# Level_Detector.net
KiCad netlist of a schematic drawn in Altium Designer
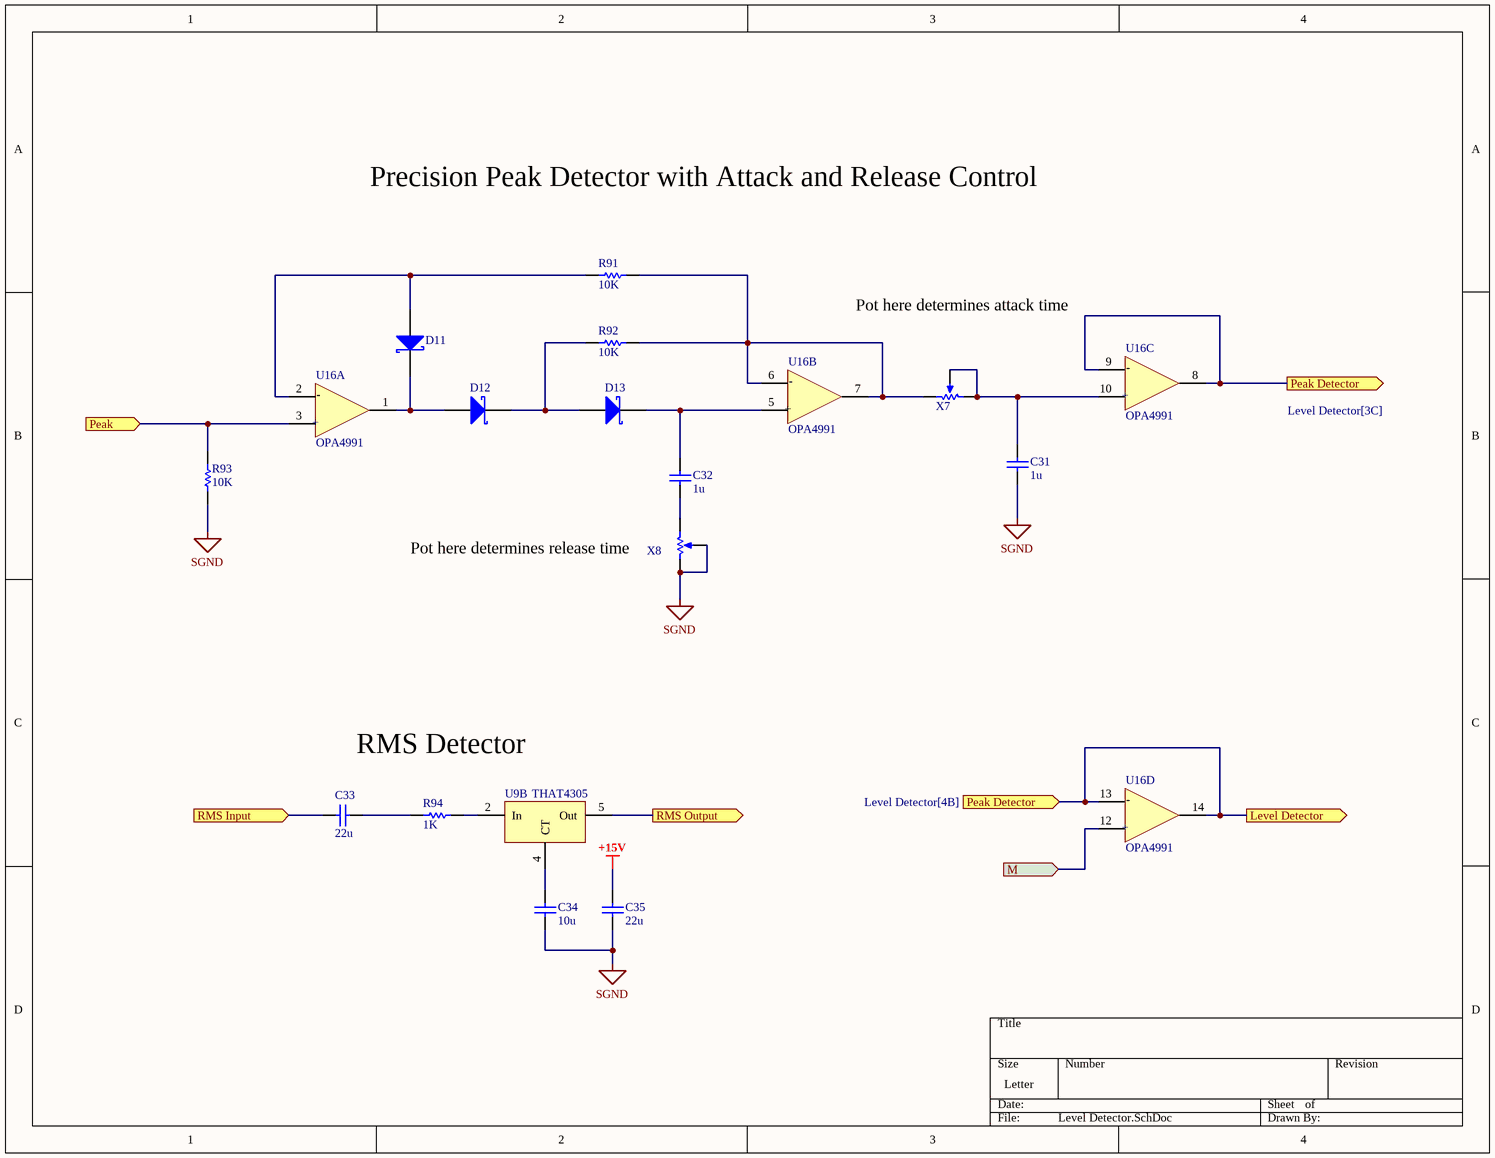
[diagram p0: Level Detector.SchDoc]

(export (version "E")
  (design (tool "Eeschema 10.0.6"))
  (components
    (comp (ref "C31")
      (value "1u")
      (description "Capacitor")
      (libsource (lib "Simulation Generic Components") (part "Capacitor"))
    )
    (comp (ref "C32")
      (value "1u")
      (description "Capacitor")
      (libsource (lib "Simulation Generic Components") (part "Capacitor"))
    )
    (comp (ref "C33")
      (value "22u")
      (description "Capacitor")
      (libsource (lib "Simulation Generic Components") (part "Capacitor"))
    )
    (comp (ref "C34")
      (value "10u")
      (description "Capacitor")
      (libsource (lib "Simulation Generic Components") (part "Capacitor"))
    )
    (comp (ref "C35")
      (value "22u")
      (description "Capacitor")
      (libsource (lib "Simulation Generic Components") (part "Capacitor"))
    )
    (comp (ref "D11")
      (value "Schottky Diode")
      (libsource (lib "Simulation Generic Components") (part "Schottky Diode"))
    )
    (comp (ref "D12")
      (value "Schottky Diode")
      (libsource (lib "Simulation Generic Components") (part "Schottky Diode"))
    )
    (comp (ref "D13")
      (value "Schottky Diode")
      (libsource (lib "Simulation Generic Components") (part "Schottky Diode"))
    )
    (comp (ref "R91")
      (value "10K")
      (description "Resistor")
      (libsource (lib "Simulation Generic Components") (part "Resistor"))
    )
    (comp (ref "R92")
      (value "10K")
      (description "Resistor")
      (libsource (lib "Simulation Generic Components") (part "Resistor"))
    )
    (comp (ref "R93")
      (value "10K")
      (description "Resistor")
      (libsource (lib "Simulation Generic Components") (part "Resistor"))
    )
    (comp (ref "R94")
      (value "1K")
      (description "Resistor")
      (libsource (lib "Simulation Generic Components") (part "Resistor"))
    )
    (comp (ref "U9")
      (value "THAT4305")
      (footprint "QSOP-16")
      (description "Pre-trimmed Analog Engine® Dynamics Processor IC")
      (libsource (lib "DRC") (part "4305Q16-U"))
    )
    (comp (ref "U16")
      (value "OPA4991")
      (footprint "FP-D0014A-IPC_B")
      (description "40-V, DUAL 4.5MHZ, RAIL-TO-RAIL")
      (libsource (lib "DRC") (part "OPA4991IDR"))
    )
    (comp (ref "X7")
      (value "Potentiometer")
      (libsource (lib "Simulation Generic Components") (part "Potentiometer"))
    )
    (comp (ref "X8")
      (value "Potentiometer")
      (libsource (lib "Simulation Generic Components") (part "Potentiometer"))
    )
  )
  (nets
    (net (code "1") (name "+15V") (class "Default")
      (node (ref "C35") (pin "2") (pinfunction "2_2") (pintype "passive"))
    )
    (net (code "2") (name "/Level Detector") (class "Default")
      (node (ref "U16") (pin "13") (pinfunction "IN4-_13") (pintype "tri_state"))
      (node (ref "U16") (pin "14") (pinfunction "OUT4_14") (pintype "passive"))
      (node (ref "U16") (pin "8") (pinfunction "OUT3_8") (pintype "passive"))
      (node (ref "U16") (pin "9") (pinfunction "IN3-_9") (pintype "tri_state"))
    )
    (net (code "3") (name "/M") (class "Default")
      (node (ref "U16") (pin "12") (pinfunction "IN4+_12") (pintype "tri_state"))
    )
    (net (code "4") (name "/Peak") (class "Default")
      (node (ref "R93") (pin "2") (pinfunction "2_2") (pintype "passive"))
      (node (ref "U16") (pin "3") (pinfunction "IN1+_3") (pintype "tri_state"))
    )
    (net (code "5") (name "/RMS Input") (class "Default")
      (node (ref "C33") (pin "2") (pinfunction "2_2") (pintype "passive"))
    )
    (net (code "6") (name "/RMS Output") (class "Default")
      (node (ref "U9") (pin "5") (pinfunction "Out_5") (pintype "passive"))
    )
    (net (code "7") (name "Net-(C33-Pad1)") (class "Default")
      (node (ref "C33") (pin "1") (pinfunction "1_1") (pintype "passive"))
      (node (ref "R94") (pin "1") (pinfunction "1_1") (pintype "passive"))
    )
    (net (code "8") (name "Net-(D11-A)") (class "Default")
      (node (ref "D11") (pin "1") (pinfunction "A_1") (pintype "passive"))
      (node (ref "R91") (pin "2") (pinfunction "2_2") (pintype "passive"))
      (node (ref "U16") (pin "2") (pinfunction "IN1-_2") (pintype "tri_state"))
    )
    (net (code "9") (name "Net-(D11-K)") (class "Default")
      (node (ref "D11") (pin "2") (pinfunction "K_2") (pintype "passive"))
      (node (ref "D12") (pin "1") (pinfunction "A_1") (pintype "passive"))
      (node (ref "U16") (pin "1") (pinfunction "OUT1_1") (pintype "passive"))
    )
    (net (code "10") (name "Net-(D12-K)") (class "Default")
      (node (ref "D12") (pin "2") (pinfunction "K_2") (pintype "passive"))
      (node (ref "D13") (pin "1") (pinfunction "A_1") (pintype "passive"))
      (node (ref "R92") (pin "2") (pinfunction "2_2") (pintype "passive"))
    )
    (net (code "11") (name "Net-(D13-K)") (class "Default")
      (node (ref "C32") (pin "2") (pinfunction "2_2") (pintype "passive"))
      (node (ref "D13") (pin "2") (pinfunction "K_2") (pintype "passive"))
      (node (ref "U16") (pin "5") (pinfunction "IN2+_5") (pintype "tri_state"))
    )
    (net (code "12") (name "Net-(U9B-CT)") (class "Default")
      (node (ref "C34") (pin "2") (pinfunction "2_2") (pintype "passive"))
      (node (ref "U9") (pin "4") (pinfunction "CT_4") (pintype "passive"))
    )
    (net (code "13") (name "Net-(U9B-In)") (class "Default")
      (node (ref "R94") (pin "2") (pinfunction "2_2") (pintype "passive"))
      (node (ref "U9") (pin "2") (pinfunction "In_2") (pintype "passive"))
    )
    (net (code "14") (name "Net-(U16B-IN2-)") (class "Default")
      (node (ref "R91") (pin "1") (pinfunction "1_1") (pintype "passive"))
      (node (ref "R92") (pin "1") (pinfunction "1_1") (pintype "passive"))
      (node (ref "U16") (pin "6") (pinfunction "IN2-_6") (pintype "tri_state"))
      (node (ref "U16") (pin "7") (pinfunction "OUT2_7") (pintype "passive"))
      (node (ref "X7") (pin "1") (pinfunction "TOP_1") (pintype "passive"))
    )
    (net (code "15") (name "Net-(U16C-IN3+)") (class "Default")
      (node (ref "C31") (pin "2") (pinfunction "2_2") (pintype "passive"))
      (node (ref "U16") (pin "10") (pinfunction "IN3+_10") (pintype "tri_state"))
      (node (ref "X7") (pin "2") (pinfunction "BOT_2") (pintype "passive"))
      (node (ref "X7") (pin "3") (pinfunction "TAP_3") (pintype "passive"))
    )
    (net (code "16") (name "Net-(X8-TOP)") (class "Default")
      (node (ref "C32") (pin "1") (pinfunction "1_1") (pintype "passive"))
      (node (ref "X8") (pin "1") (pinfunction "TOP_1") (pintype "passive"))
    )
    (net (code "17") (name "SGND") (class "Default")
      (node (ref "C31") (pin "1") (pinfunction "1_1") (pintype "passive"))
      (node (ref "C34") (pin "1") (pinfunction "1_1") (pintype "passive"))
      (node (ref "C35") (pin "1") (pinfunction "1_1") (pintype "passive"))
      (node (ref "R93") (pin "1") (pinfunction "1_1") (pintype "passive"))
      (node (ref "X8") (pin "2") (pinfunction "BOT_2") (pintype "passive"))
      (node (ref "X8") (pin "3") (pinfunction "TAP_3") (pintype "passive"))
    )
  )
)
